# adxl375.net
KiCad netlist of a schematic drawn in Altium Designer
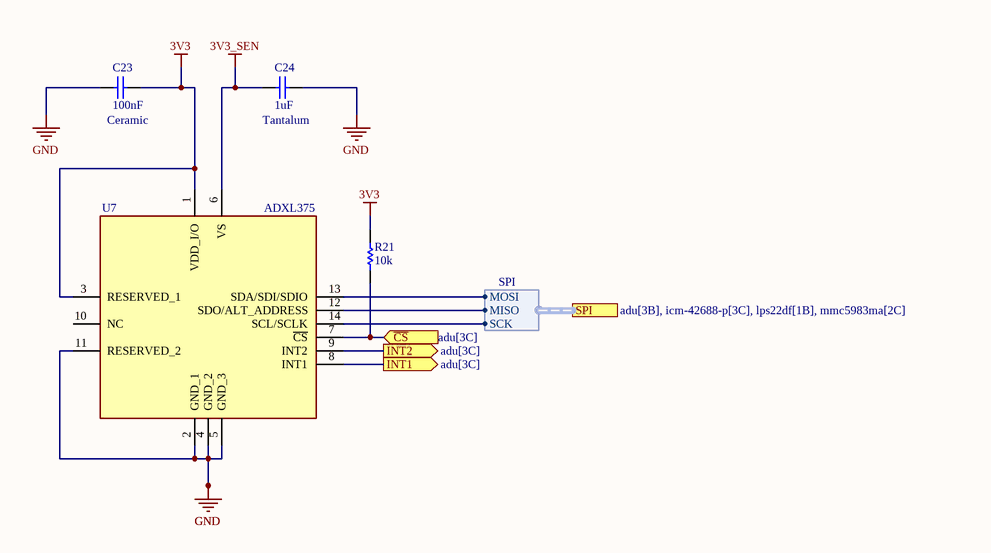
[diagram p0: adxl375.SchDoc]

(export (version "E")
  (design (tool "Eeschema 10.0.6"))
  (components
    (comp (ref "C23")
      (value "100nF")
      (footprint "CAPC0603X33N")
      (description "Capacitor")
      (fields (field (name "Comment") "Cap") (field (name "PUBLISHER") "Altium Limited"))
      (libsource (lib "Miscellaneous Devices") (part "Cap"))
    )
    (comp (ref "C24")
      (value "1uF")
      (footprint "CAPC0603X33N")
      (description "Capacitor")
      (fields (field (name "Comment") "Cap") (field (name "PUBLISHER") "Altium Limited"))
      (libsource (lib "Miscellaneous Devices") (part "Cap"))
    )
    (comp (ref "R21")
      (value "10k")
      (footprint "RES-0603")
      (description "Resistor")
      (libsource (lib "drfc_schlib") (part "Resistor"))
    )
    (comp (ref "U7")
      (value "ADXL375")
      (footprint "ADXL375")
      (description "3-Axis, ±200 g\r\nDigital MEMS Accelerometer")
      (libsource (lib "drfc_schlib") (part "ADXL375"))
    )
  )
  (nets
    (net (code "2") (name "/INT1") (class "Default")
      (node (ref "U7") (pin "8") (pinfunction "INT1_8") (pintype "passive"))
    )
    (net (code "3") (name "/INT2") (class "Default")
      (node (ref "U7") (pin "9") (pinfunction "INT2_9") (pintype "passive"))
    )
    (net (code "4") (name "/MISO") (class "Default")
      (node (ref "U7") (pin "12") (pinfunction "SDO/ALT_ADDRESS_12") (pintype "passive"))
    )
    (net (code "5") (name "/MOSI") (class "Default")
      (node (ref "U7") (pin "13") (pinfunction "SDA/SDI/SDIO_13") (pintype "passive"))
    )
    (net (code "6") (name "/SCK") (class "Default")
      (node (ref "U7") (pin "14") (pinfunction "SCL/SCLK_14") (pintype "passive"))
    )
    (net (code "8") (name "/~{CS}") (class "Default")
      (node (ref "R21") (pin "1") (pinfunction "1_1") (pintype "passive"))
      (node (ref "U7") (pin "7") (pinfunction "~{CS}_7") (pintype "passive"))
    )
    (net (code "9") (name "3V3") (class "Default")
      (node (ref "C23") (pin "1") (pinfunction "1_1") (pintype "passive"))
      (node (ref "R21") (pin "2") (pinfunction "2_2") (pintype "passive"))
      (node (ref "U7") (pin "1") (pinfunction "VDD_I/O_1") (pintype "passive"))
      (node (ref "U7") (pin "3") (pinfunction "RESERVED_1_3") (pintype "passive"))
    )
    (net (code "10") (name "3V3_SEN") (class "Default")
      (node (ref "C24") (pin "2") (pinfunction "2_2") (pintype "passive"))
      (node (ref "U7") (pin "6") (pinfunction "VS_6") (pintype "passive"))
    )
    (net (code "11") (name "GND") (class "Default")
      (node (ref "C23") (pin "2") (pinfunction "2_2") (pintype "passive"))
      (node (ref "C24") (pin "1") (pinfunction "1_1") (pintype "passive"))
      (node (ref "U7") (pin "11") (pinfunction "RESERVED_2_11") (pintype "passive"))
      (node (ref "U7") (pin "2") (pinfunction "GND_1_2") (pintype "passive"))
      (node (ref "U7") (pin "4") (pinfunction "GND_2_4") (pintype "passive"))
      (node (ref "U7") (pin "5") (pinfunction "GND_3_5") (pintype "passive"))
    )
    (net (code "12") (name "unconnected-(U7-NC-Pad10)") (class "Default")
      (node (ref "U7") (pin "10") (pinfunction "NC_10") (pintype "passive"))
    )
  )
)
